# BUMPER_SCHEMA.net
KiCad netlist of a schematic drawn in Altium Designer
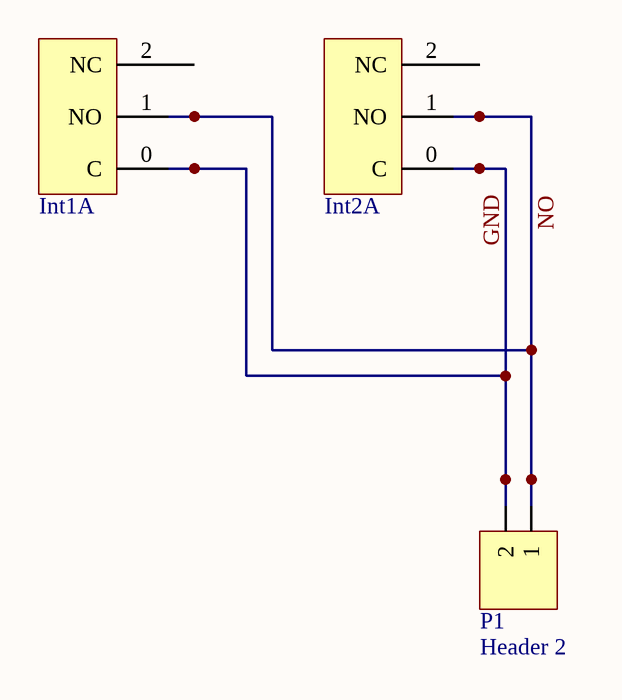
[diagram p0: BUMPER SCHEMA.SchDoc]

(export (version "E")
  (design (tool "Eeschema 10.0.6"))
  (components
    (comp (ref "Int1")
      (value "DB2C-A1RC")
      (footprint "PCBComponent_1")
      (description "Microrupteur à galet")
      (libsource (lib "Projet From Scratch to SLAM") (part "DB2C-A1RC"))
    )
    (comp (ref "Int2")
      (value "DB2C-A1RC")
      (footprint "PCBComponent_1")
      (description "Microrupteur à galet")
      (libsource (lib "Projet From Scratch to SLAM") (part "DB2C-A1RC"))
    )
    (comp (ref "P1")
      (value "Header 2")
      (footprint "HDR1X2")
      (description "Header, 2-Pin")
      (fields (field (name "PUBLISHER") "Altium Limited"))
      (libsource (lib "Miscellaneous Connectors") (part "Header 2"))
    )
  )
  (nets
    (net (code "1") (name "/GND") (class "Default")
      (node (ref "Int1") (pin "0") (pinfunction "C_0") (pintype "passive"))
      (node (ref "Int2") (pin "0") (pinfunction "C_0") (pintype "passive"))
      (node (ref "P1") (pin "2") (pinfunction "2_2") (pintype "passive"))
    )
    (net (code "2") (name "/NO") (class "Default")
      (node (ref "Int1") (pin "1") (pinfunction "NO_1") (pintype "passive"))
      (node (ref "Int2") (pin "1") (pinfunction "NO_1") (pintype "passive"))
      (node (ref "P1") (pin "1") (pinfunction "1_1") (pintype "passive"))
    )
    (net (code "3") (name "unconnected-(Int1-NC-Pad2)") (class "Default")
      (node (ref "Int1") (pin "2") (pinfunction "NC_2") (pintype "passive"))
    )
    (net (code "4") (name "unconnected-(Int2-NC-Pad2)") (class "Default")
      (node (ref "Int2") (pin "2") (pinfunction "NC_2") (pintype "passive"))
    )
  )
)
